# D-HMC194.net
KiCad netlist of a schematic drawn in Altium Designer
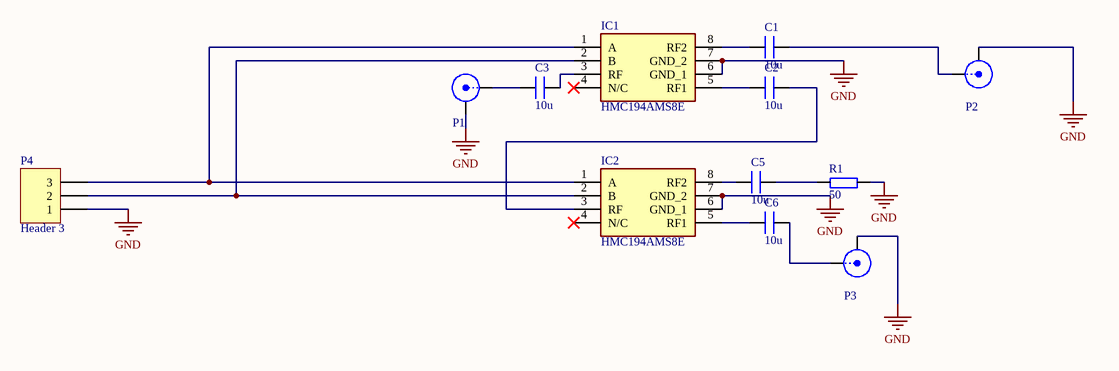
[diagram p0: D-HMC194.SchDoc]

(export (version "E")
  (design (tool "Eeschema 10.0.6"))
  (components
    (comp (ref "C1")
      (value "10u")
      (footprint "0402")
      (description "Capacitor")
      (libsource (lib "MYLIB") (part "C"))
    )
    (comp (ref "C2")
      (value "10u")
      (footprint "0402")
      (description "Capacitor")
      (libsource (lib "MYLIB") (part "C"))
    )
    (comp (ref "C3")
      (value "10u")
      (footprint "0402")
      (description "Capacitor")
      (libsource (lib "MYLIB") (part "C"))
    )
    (comp (ref "C5")
      (value "10u")
      (footprint "0402")
      (description "Capacitor")
      (libsource (lib "MYLIB") (part "C"))
    )
    (comp (ref "C6")
      (value "10u")
      (footprint "0402")
      (description "Capacitor")
      (libsource (lib "MYLIB") (part "C"))
    )
    (comp (ref "IC1")
      (value "HMC194AMS8E")
      (footprint "MYLIB:SOP65P488X110-8N")
      (description "Integrated Circuit")
      (fields (field (name "MOUSER PART NUMBER") "584-HMC194AMS8E"))
      (libsource (lib "MYLIB") (part "HMC194AMS8E"))
    )
    (comp (ref "IC2")
      (value "HMC194AMS8E")
      (footprint "MYLIB:SOP65P488X110-8N")
      (description "Integrated Circuit")
      (fields (field (name "MOUSER PART NUMBER") "584-HMC194AMS8E"))
      (libsource (lib "MYLIB") (part "HMC194AMS8E"))
    )
    (comp (ref "P1")
      (value "SMA")
      (footprint "SMA")
      (description "SMA Connector")
      (libsource (lib "MYLIB") (part "SMA"))
    )
    (comp (ref "P2")
      (value "SMA")
      (footprint "SMA")
      (description "SMA Connector")
      (libsource (lib "MYLIB") (part "SMA"))
    )
    (comp (ref "P3")
      (value "SMA")
      (footprint "SMA")
      (description "SMA Connector")
      (libsource (lib "MYLIB") (part "SMA"))
    )
    (comp (ref "P4")
      (value "Header 3")
      (footprint "HDR1X3")
      (description "Header, 3-Pin")
      (fields (field (name "PUBLISHER") "Altium Limited"))
      (libsource (lib "Miscellaneous Connectors") (part "Header 3"))
    )
    (comp (ref "R1")
      (value "50")
      (footprint "0603R")
      (description "Resistor")
      (libsource (lib "MYLIB") (part "Resistor"))
    )
  )
  (nets
    (net (code "1") (name "GND") (class "Default")
      (node (ref "IC1") (pin "6") (pinfunction "GND_1_6") (pintype "passive"))
      (node (ref "IC1") (pin "7") (pinfunction "GND_2_7") (pintype "passive"))
      (node (ref "IC2") (pin "6") (pinfunction "GND_1_6") (pintype "passive"))
      (node (ref "IC2") (pin "7") (pinfunction "GND_2_7") (pintype "passive"))
      (node (ref "P1") (pin "2") (pinfunction "Y_2") (pintype "passive"))
      (node (ref "P2") (pin "2") (pinfunction "Y_2") (pintype "passive"))
      (node (ref "P3") (pin "2") (pinfunction "Y_2") (pintype "passive"))
      (node (ref "P4") (pin "1") (pinfunction "1_1") (pintype "passive"))
      (node (ref "R1") (pin "2") (pintype "passive"))
    )
    (net (code "2") (name "Net-(C5-Pad2)") (class "Default")
      (node (ref "C5") (pin "2") (pintype "passive"))
      (node (ref "R1") (pin "1") (pintype "passive"))
    )
    (net (code "3") (name "Net-(IC1-A)") (class "Default")
      (node (ref "IC1") (pin "1") (pinfunction "A_1") (pintype "passive"))
      (node (ref "IC2") (pin "1") (pinfunction "A_1") (pintype "passive"))
      (node (ref "P4") (pin "3") (pinfunction "3_3") (pintype "passive"))
    )
    (net (code "4") (name "Net-(IC1-B)") (class "Default")
      (node (ref "IC1") (pin "2") (pinfunction "B_2") (pintype "passive"))
      (node (ref "IC2") (pin "2") (pinfunction "B_2") (pintype "passive"))
      (node (ref "P4") (pin "2") (pinfunction "2_2") (pintype "passive"))
    )
    (net (code "5") (name "Net-(IC1-RF)") (class "Default")
      (node (ref "C3") (pin "2") (pintype "passive"))
      (node (ref "IC1") (pin "3") (pinfunction "RF_3") (pintype "passive"))
    )
    (net (code "6") (name "Net-(IC1-RF1)") (class "Default")
      (node (ref "C2") (pin "1") (pintype "passive"))
      (node (ref "IC1") (pin "5") (pinfunction "RF1_5") (pintype "passive"))
    )
    (net (code "7") (name "Net-(IC1-RF2)") (class "Default")
      (node (ref "C1") (pin "1") (pintype "passive"))
      (node (ref "IC1") (pin "8") (pinfunction "RF2_8") (pintype "passive"))
    )
    (net (code "8") (name "Net-(IC2-RF)") (class "Default")
      (node (ref "C2") (pin "2") (pintype "passive"))
      (node (ref "IC2") (pin "3") (pinfunction "RF_3") (pintype "passive"))
    )
    (net (code "9") (name "Net-(IC2-RF1)") (class "Default")
      (node (ref "C6") (pin "1") (pintype "passive"))
      (node (ref "IC2") (pin "5") (pinfunction "RF1_5") (pintype "passive"))
    )
    (net (code "10") (name "Net-(IC2-RF2)") (class "Default")
      (node (ref "C5") (pin "1") (pintype "passive"))
      (node (ref "IC2") (pin "8") (pinfunction "RF2_8") (pintype "passive"))
    )
    (net (code "11") (name "Net-(P1-X)") (class "Default")
      (node (ref "C3") (pin "1") (pintype "passive"))
      (node (ref "P1") (pin "1") (pinfunction "X_1") (pintype "passive"))
    )
    (net (code "12") (name "Net-(P2-X)") (class "Default")
      (node (ref "C1") (pin "2") (pintype "passive"))
      (node (ref "P2") (pin "1") (pinfunction "X_1") (pintype "passive"))
    )
    (net (code "13") (name "Net-(P3-X)") (class "Default")
      (node (ref "C6") (pin "2") (pintype "passive"))
      (node (ref "P3") (pin "1") (pinfunction "X_1") (pintype "passive"))
    )
    (net (code "14") (name "unconnected-(IC1-N{slash}C-Pad4)") (class "Default")
      (node (ref "IC1") (pin "4") (pinfunction "N/C_4") (pintype "passive+no_connect"))
    )
    (net (code "15") (name "unconnected-(IC2-N{slash}C-Pad4)") (class "Default")
      (node (ref "IC2") (pin "4") (pinfunction "N/C_4") (pintype "passive+no_connect"))
    )
  )
)
